# TTL_TO_RS232.net
KiCad netlist of a schematic drawn in Altium Designer
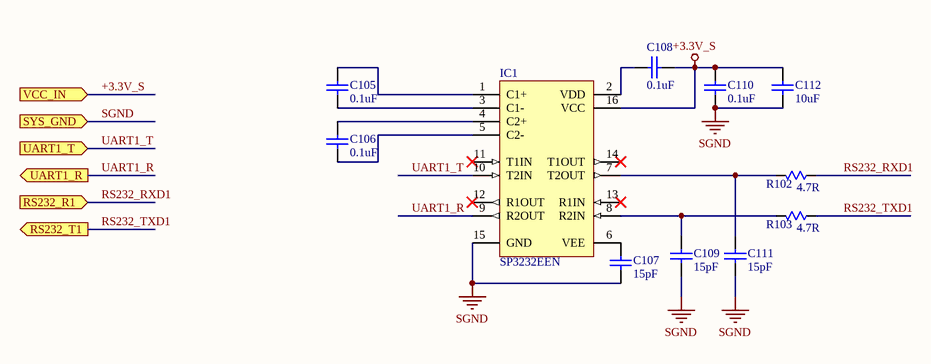
[diagram p0: TTL_TO_RS232.SchDoc]

(export (version "E")
  (design (tool "Eeschema 10.0.6"))
  (components
    (comp (ref "C105")
      (value "0.1uF")
      (footprint "C0805")
      (description "CAP")
      (fields (field (name "PUBLISHER") "Altium Limited"))
      (libsource (lib "Passive Components Class") (part "CAP"))
    )
    (comp (ref "C106")
      (value "0.1uF")
      (footprint "C0805")
      (description "CAP")
      (fields (field (name "PUBLISHER") "Altium Limited"))
      (libsource (lib "Passive Components Class") (part "CAP"))
    )
    (comp (ref "C107")
      (value "15pF")
      (footprint "C0805")
      (description "Capacitor")
      (fields (field (name "PUBLISHER") "Altium Limited"))
      (libsource (lib "Miscellaneous Devices") (part "Cap"))
    )
    (comp (ref "C108")
      (value "0.1uF")
      (footprint "C0805")
      (description "CAP")
      (fields (field (name "PUBLISHER") "Altium Limited"))
      (libsource (lib "Passive Components Class") (part "CAP"))
    )
    (comp (ref "C109")
      (value "15pF")
      (footprint "C0805")
      (description "Capacitor")
      (fields (field (name "PUBLISHER") "Altium Limited"))
      (libsource (lib "Miscellaneous Devices") (part "Cap"))
    )
    (comp (ref "C110")
      (value "0.1uF")
      (footprint "C0805")
      (description "CAP")
      (fields (field (name "PUBLISHER") "Altium Limited"))
      (libsource (lib "Passive Components Class") (part "CAP"))
    )
    (comp (ref "C111")
      (value "15pF")
      (footprint "C0805")
      (description "Capacitor")
      (fields (field (name "PUBLISHER") "Altium Limited"))
      (libsource (lib "Miscellaneous Devices") (part "Cap"))
    )
    (comp (ref "C112")
      (value "10uF")
      (footprint "C1206")
      (description "CAP")
      (fields (field (name "PUBLISHER") "Altium Limited"))
      (libsource (lib "Passive Components Class") (part "CAP"))
    )
    (comp (ref "IC1")
      (value "SP3232EEN")
      (footprint "SO16-150")
      (description "+5V Powered, Multi-Channel RS-232 Driver/Receiver")
      (fields
        (field (name "MANUFACTURER") "Maxim")
        (field (name "PUBLISHER") "Altium Hobart Technology Centre")
      )
      (libsource (lib "Maxim Communication Transceiver") (part "MAX232ACPE"))
    )
    (comp (ref "R102")
      (value "4.7R")
      (footprint "R0805")
      (description "Resistor")
      (fields (field (name "PUBLISHER") "Altium Limited"))
      (libsource (lib "Passive Components Class") (part "Res"))
    )
    (comp (ref "R103")
      (value "4.7R")
      (footprint "R0805")
      (description "Resistor")
      (fields (field (name "PUBLISHER") "Altium Limited"))
      (libsource (lib "Temp") (part "Res"))
    )
  )
  (nets
    (net (code "1") (name "+3.3V_S") (class "Default")
      (node (ref "C108") (pin "1") (pinfunction "1_1") (pintype "passive"))
      (node (ref "C110") (pin "2") (pinfunction "2_2") (pintype "passive"))
      (node (ref "C112") (pin "2") (pinfunction "2_2") (pintype "passive"))
      (node (ref "IC1") (pin "16") (pinfunction "VCC_16") (pintype "power_in"))
    )
    (net (code "2") (name "/RS232_RXD1") (class "Default")
      (node (ref "R102") (pin "2") (pinfunction "2_2") (pintype "passive"))
    )
    (net (code "3") (name "/RS232_TXD1") (class "Default")
      (node (ref "R103") (pin "2") (pinfunction "2_2") (pintype "passive"))
    )
    (net (code "4") (name "/UART1_R") (class "Default")
      (node (ref "IC1") (pin "9") (pinfunction "R2OUT_9") (pintype "output"))
    )
    (net (code "5") (name "/UART1_T") (class "Default")
      (node (ref "IC1") (pin "10") (pinfunction "T2IN_10") (pintype "input"))
    )
    (net (code "6") (name "Net-(IC1-C1+)") (class "Default")
      (node (ref "C105") (pin "2") (pinfunction "2_2") (pintype "passive"))
      (node (ref "IC1") (pin "1") (pinfunction "C1+_1") (pintype "passive"))
    )
    (net (code "7") (name "Net-(IC1-C1-)") (class "Default")
      (node (ref "C105") (pin "1") (pinfunction "1_1") (pintype "passive"))
      (node (ref "IC1") (pin "3") (pinfunction "C1-_3") (pintype "passive"))
    )
    (net (code "8") (name "Net-(IC1-C2+)") (class "Default")
      (node (ref "C106") (pin "2") (pinfunction "2_2") (pintype "passive"))
      (node (ref "IC1") (pin "4") (pinfunction "C2+_4") (pintype "passive"))
    )
    (net (code "9") (name "Net-(IC1-C2-)") (class "Default")
      (node (ref "C106") (pin "1") (pinfunction "1_1") (pintype "passive"))
      (node (ref "IC1") (pin "5") (pinfunction "C2-_5") (pintype "passive"))
    )
    (net (code "10") (name "Net-(IC1-R2IN)") (class "Default")
      (node (ref "C109") (pin "1") (pinfunction "1_1") (pintype "passive"))
      (node (ref "IC1") (pin "8") (pinfunction "R2IN_8") (pintype "input"))
      (node (ref "R103") (pin "1") (pinfunction "1_1") (pintype "passive"))
    )
    (net (code "11") (name "Net-(IC1-T2OUT)") (class "Default")
      (node (ref "C111") (pin "1") (pinfunction "1_1") (pintype "passive"))
      (node (ref "IC1") (pin "7") (pinfunction "T2OUT_7") (pintype "output"))
      (node (ref "R102") (pin "1") (pinfunction "1_1") (pintype "passive"))
    )
    (net (code "12") (name "Net-(IC1-VDD)") (class "Default")
      (node (ref "C108") (pin "2") (pinfunction "2_2") (pintype "passive"))
      (node (ref "IC1") (pin "2") (pinfunction "VDD_2") (pintype "power_in"))
    )
    (net (code "13") (name "Net-(IC1-VEE)") (class "Default")
      (node (ref "C107") (pin "1") (pinfunction "1_1") (pintype "passive"))
      (node (ref "IC1") (pin "6") (pinfunction "VEE_6") (pintype "power_in"))
    )
    (net (code "14") (name "SGND") (class "Default")
      (node (ref "C107") (pin "2") (pinfunction "2_2") (pintype "passive"))
      (node (ref "C109") (pin "2") (pinfunction "2_2") (pintype "passive"))
      (node (ref "C110") (pin "1") (pinfunction "1_1") (pintype "passive"))
      (node (ref "C111") (pin "2") (pinfunction "2_2") (pintype "passive"))
      (node (ref "C112") (pin "1") (pinfunction "1_1") (pintype "passive"))
      (node (ref "IC1") (pin "15") (pinfunction "GND_15") (pintype "power_in"))
    )
    (net (code "15") (name "unconnected-(IC1-R1IN-Pad13)") (class "Default")
      (node (ref "IC1") (pin "13") (pinfunction "R1IN_13") (pintype "input+no_connect"))
    )
    (net (code "16") (name "unconnected-(IC1-R1OUT-Pad12)") (class "Default")
      (node (ref "IC1") (pin "12") (pinfunction "R1OUT_12") (pintype "output+no_connect"))
    )
    (net (code "17") (name "unconnected-(IC1-T1IN-Pad11)") (class "Default")
      (node (ref "IC1") (pin "11") (pinfunction "T1IN_11") (pintype "input+no_connect"))
    )
    (net (code "18") (name "unconnected-(IC1-T1OUT-Pad14)") (class "Default")
      (node (ref "IC1") (pin "14") (pinfunction "T1OUT_14") (pintype "output+no_connect"))
    )
  )
)
